# EncLickDrv_J0104132C-ESPrevC.net
KiCad netlist of a schematic drawn in EAGLE
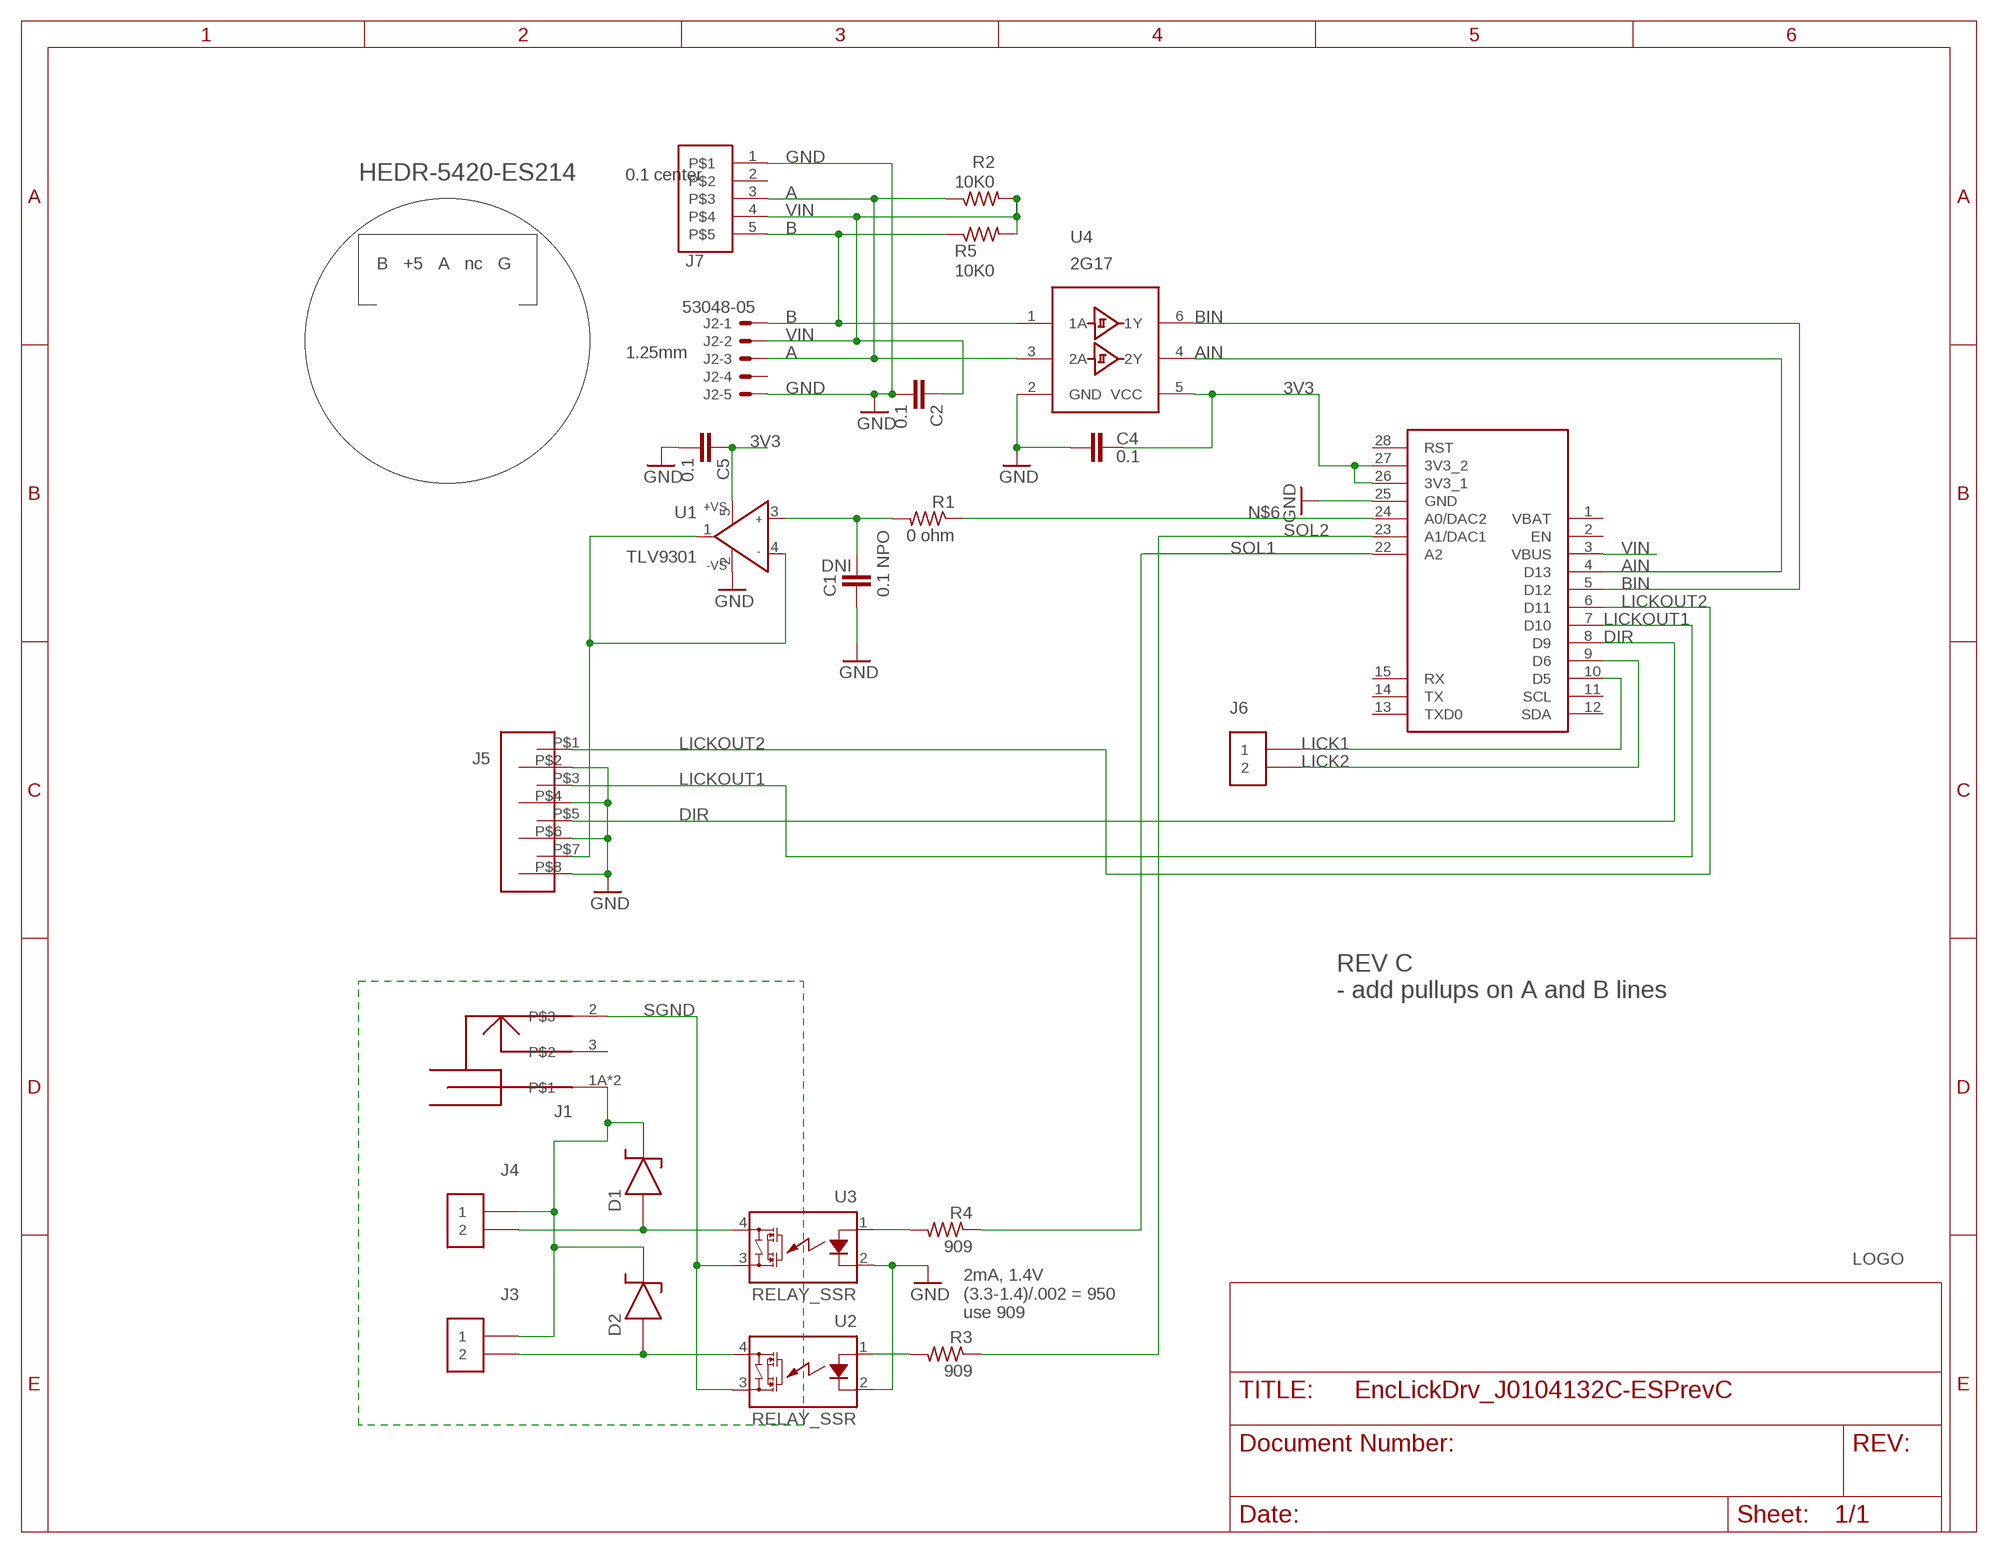
[diagram p0: schematic, sheet 1]

(export (version "E")
  (design (tool "Eeschema 10.0.6"))
  (components
    (comp (ref "C1")
      (value "0.1 NPO")
      (footprint "eagle-import:1206S")
      (libsource (lib "eagle-import") (part "CAPS1206S"))
    )
    (comp (ref "C2")
      (value "0.1")
      (footprint "eagle-import:0603S")
      (libsource (lib "eagle-import") (part "CAPS0603S"))
    )
    (comp (ref "C4")
      (value "0.1")
      (footprint "eagle-import:0603S")
      (libsource (lib "eagle-import") (part "CAPS0603S"))
    )
    (comp (ref "C5")
      (value "0.1")
      (footprint "eagle-import:0603S")
      (libsource (lib "eagle-import") (part "CAPS0603S"))
    )
    (comp (ref "D1")
      (value "DIODE_SCHOTTKYPWRDI-123")
      (footprint "eagle-import:PWRDI-123")
      (libsource (lib "eagle-import") (part "DIODE_SCHOTTKYPWRDI-123"))
    )
    (comp (ref "D2")
      (value "DIODE_SCHOTTKYPWRDI-123")
      (footprint "eagle-import:PWRDI-123")
      (libsource (lib "eagle-import") (part "DIODE_SCHOTTKYPWRDI-123"))
    )
    (comp (ref "J1")
      (value "POWER_JACK_SHUNTPJ-002")
      (footprint "eagle-import:PJ-002")
      (libsource (lib "eagle-import") (part "POWER_JACK_SHUNTPJ-002"))
    )
    (comp (ref "J2")
      (value "53048-05")
      (footprint "eagle-import:53048-05")
      (fields (field (name "MF") "MOLEX") (field (name "MPN") "53048-0510"))
      (libsource (lib "eagle-import") (part "53?-05048"))
    )
    (comp (ref "J3")
      (value "CON21881558")
      (footprint "eagle-import:1881558")
      (libsource (lib "eagle-import") (part "CON21881558"))
    )
    (comp (ref "J4")
      (value "CON21881558")
      (footprint "eagle-import:1881558")
      (libsource (lib "eagle-import") (part "CON21881558"))
    )
    (comp (ref "J5")
      (value "CON81844743")
      (footprint "eagle-import:1844743")
      (libsource (lib "eagle-import") (part "CON81844743"))
    )
    (comp (ref "J6")
      (value "CON21881558")
      (footprint "eagle-import:1881558")
      (libsource (lib "eagle-import") (part "CON21881558"))
    )
    (comp (ref "J7")
      (value "CON5104361-4")
      (footprint "eagle-import:104361-4")
      (libsource (lib "eagle-import") (part "CON5104361-4"))
    )
    (comp (ref "M1")
      (value "ESP32=S2-REV-TFT-NO16-21")
      (footprint "eagle-import:ESP32-S2-REV-TFT-NO16-21")
      (libsource (lib "eagle-import") (part "ESP32=S2-REV-TFT-NO16-21"))
    )
    (comp (ref "R1")
      (value "0 ohm")
      (footprint "eagle-import:0805S")
      (libsource (lib "eagle-import") (part "RESISTOR_SM0805S"))
    )
    (comp (ref "R2")
      (value "10K0")
      (footprint "eagle-import:0805S")
      (libsource (lib "eagle-import") (part "RESISTOR_SM0805S"))
    )
    (comp (ref "R3")
      (value "909")
      (footprint "eagle-import:0805S")
      (libsource (lib "eagle-import") (part "RESISTOR_SM0805S"))
    )
    (comp (ref "R4")
      (value "909")
      (footprint "eagle-import:0805S")
      (libsource (lib "eagle-import") (part "RESISTOR_SM0805S"))
    )
    (comp (ref "R5")
      (value "10K0")
      (footprint "eagle-import:0805S")
      (libsource (lib "eagle-import") (part "RESISTOR_SM0805S"))
    )
    (comp (ref "U$1")
      (value "JFRC-LOGOLOGO_OP")
      (footprint "eagle-import:LOGO_BMP_OP")
      (libsource (lib "eagle-import") (part "JFRC-LOGOLOGO_OP"))
    )
    (comp (ref "U1")
      (value "TLV9301")
      (footprint "eagle-import:SOT23-5")
      (fields (field (name "MF") "ALTERA CORPORATION") (field (name "MPN") "AD8065ARTZ-REEL7"))
      (libsource (lib "eagle-import") (part "AD8065RT"))
    )
    (comp (ref "U2")
      (value "RELAY_SSR")
      (footprint "eagle-import:SSR_SOIP")
      (libsource (lib "eagle-import") (part "RELAY_SSR"))
    )
    (comp (ref "U3")
      (value "RELAY_SSR")
      (footprint "eagle-import:SSR_SOIP")
      (libsource (lib "eagle-import") (part "RELAY_SSR"))
    )
    (comp (ref "U4")
      (value "2G17")
      (footprint "eagle-import:SOT23-6")
      (libsource (lib "eagle-import") (part "2G17"))
    )
  )
  (nets
    (net (code "1") (name "/3V3") (class "Default")
      (node (ref "C4") (pin "1") (pinfunction "1_1") (pintype "passive"))
      (node (ref "C5") (pin "1") (pinfunction "1_1") (pintype "passive"))
      (node (ref "M1") (pin "26") (pinfunction "3V3_1_26") (pintype "bidirectional"))
      (node (ref "M1") (pin "27") (pinfunction "3V3_2_27") (pintype "bidirectional"))
      (node (ref "U1") (pin "5") (pinfunction "+VS_5") (pintype "input"))
      (node (ref "U4") (pin "5") (pinfunction "VCC_5") (pintype "bidirectional"))
    )
    (net (code "2") (name "/A") (class "Default")
      (node (ref "J2") (pin "3") (pinfunction "S_3") (pintype "passive"))
      (node (ref "J7") (pin "3") (pinfunction "P$3_3") (pintype "bidirectional"))
      (node (ref "R2") (pin "1") (pinfunction "1_1") (pintype "passive"))
      (node (ref "U4") (pin "3") (pinfunction "2A_3") (pintype "bidirectional"))
    )
    (net (code "3") (name "/AIN") (class "Default")
      (node (ref "M1") (pin "4") (pinfunction "D13_4") (pintype "bidirectional"))
      (node (ref "U4") (pin "4") (pinfunction "2Y_4") (pintype "bidirectional"))
    )
    (net (code "4") (name "/B") (class "Default")
      (node (ref "J2") (pin "1") (pinfunction "S_1") (pintype "passive"))
      (node (ref "J7") (pin "5") (pinfunction "P$5_5") (pintype "bidirectional"))
      (node (ref "R5") (pin "1") (pinfunction "1_1") (pintype "passive"))
      (node (ref "U4") (pin "1") (pinfunction "1A_1") (pintype "bidirectional"))
    )
    (net (code "5") (name "/BIN") (class "Default")
      (node (ref "M1") (pin "5") (pinfunction "D12_5") (pintype "bidirectional"))
      (node (ref "U4") (pin "6") (pinfunction "1Y_6") (pintype "bidirectional"))
    )
    (net (code "6") (name "/DIR") (class "Default")
      (node (ref "J5") (pin "P$5") (pinfunction "5_P$5") (pintype "bidirectional"))
      (node (ref "M1") (pin "8") (pinfunction "D9_8") (pintype "bidirectional"))
    )
    (net (code "7") (name "/LICK1") (class "Default")
      (node (ref "J6") (pin "1") (pinfunction "1_1") (pintype "bidirectional"))
      (node (ref "M1") (pin "10") (pinfunction "D5_10") (pintype "bidirectional"))
    )
    (net (code "8") (name "/LICK2") (class "Default")
      (node (ref "J6") (pin "2") (pinfunction "2_2") (pintype "bidirectional"))
      (node (ref "M1") (pin "9") (pinfunction "D6_9") (pintype "bidirectional"))
    )
    (net (code "9") (name "/LICKOUT1") (class "Default")
      (node (ref "J5") (pin "P$3") (pinfunction "3_P$3") (pintype "bidirectional"))
      (node (ref "M1") (pin "7") (pinfunction "D10_7") (pintype "bidirectional"))
    )
    (net (code "10") (name "/LICKOUT2") (class "Default")
      (node (ref "J5") (pin "P$1") (pinfunction "1_P$1") (pintype "bidirectional"))
      (node (ref "M1") (pin "6") (pinfunction "D11_6") (pintype "bidirectional"))
    )
    (net (code "11") (name "/N$6") (class "Default")
      (node (ref "M1") (pin "24") (pinfunction "A0/DAC2_24") (pintype "bidirectional"))
      (node (ref "R1") (pin "1") (pinfunction "1_1") (pintype "passive"))
    )
    (net (code "12") (name "/SGND") (class "Default")
      (node (ref "J1") (pin "2") (pinfunction "P$3_2") (pintype "bidirectional"))
      (node (ref "U2") (pin "3") (pinfunction "DS2_3") (pintype "passive"))
      (node (ref "U3") (pin "3") (pinfunction "DS2_3") (pintype "passive"))
    )
    (net (code "13") (name "/SOL1") (class "Default")
      (node (ref "M1") (pin "22") (pinfunction "A2_22") (pintype "bidirectional"))
      (node (ref "R4") (pin "1") (pinfunction "1_1") (pintype "passive"))
    )
    (net (code "14") (name "/SOL2") (class "Default")
      (node (ref "M1") (pin "23") (pinfunction "A1/DAC1_23") (pintype "bidirectional"))
      (node (ref "R3") (pin "1") (pinfunction "1_1") (pintype "passive"))
    )
    (net (code "15") (name "/VIN") (class "Default")
      (node (ref "C2") (pin "1") (pinfunction "1_1") (pintype "passive"))
      (node (ref "J2") (pin "2") (pinfunction "S_2") (pintype "passive"))
      (node (ref "J7") (pin "4") (pinfunction "P$4_4") (pintype "bidirectional"))
      (node (ref "M1") (pin "3") (pinfunction "VBUS_3") (pintype "bidirectional"))
      (node (ref "R2") (pin "2") (pinfunction "2_2") (pintype "passive"))
      (node (ref "R5") (pin "2") (pinfunction "2_2") (pintype "passive"))
    )
    (net (code "16") (name "GND") (class "Default")
      (node (ref "C1") (pin "2") (pinfunction "2_2") (pintype "passive"))
      (node (ref "C2") (pin "2") (pinfunction "2_2") (pintype "passive"))
      (node (ref "C4") (pin "2") (pinfunction "2_2") (pintype "passive"))
      (node (ref "C5") (pin "2") (pinfunction "2_2") (pintype "passive"))
      (node (ref "J2") (pin "5") (pinfunction "S_5") (pintype "passive"))
      (node (ref "J5") (pin "P$2") (pinfunction "2_P$2") (pintype "bidirectional"))
      (node (ref "J5") (pin "P$4") (pinfunction "4_P$4") (pintype "bidirectional"))
      (node (ref "J5") (pin "P$6") (pinfunction "6_P$6") (pintype "bidirectional"))
      (node (ref "J5") (pin "P$8") (pinfunction "8_P$8") (pintype "bidirectional"))
      (node (ref "J7") (pin "1") (pinfunction "P$1_1") (pintype "bidirectional"))
      (node (ref "M1") (pin "25") (pinfunction "GND_25") (pintype "bidirectional"))
      (node (ref "U1") (pin "2") (pinfunction "-VS_2") (pintype "input"))
      (node (ref "U2") (pin "2") (pinfunction "K_2") (pintype "passive"))
      (node (ref "U3") (pin "2") (pinfunction "K_2") (pintype "passive"))
      (node (ref "U4") (pin "2") (pinfunction "GND_2") (pintype "bidirectional"))
    )
    (net (code "17") (name "Net-(D1-PadK)") (class "Default")
      (node (ref "D1") (pin "K") (pinfunction "K_K") (pintype "bidirectional"))
      (node (ref "D2") (pin "K") (pinfunction "K_K") (pintype "bidirectional"))
      (node (ref "J1") (pin "1A") (pinfunction "P$1_1A") (pintype "bidirectional"))
      (node (ref "J1") (pin "1B") (pinfunction "P$1_1B") (pintype "bidirectional"))
      (node (ref "J3") (pin "1") (pinfunction "1_1") (pintype "bidirectional"))
      (node (ref "J4") (pin "1") (pinfunction "1_1") (pintype "bidirectional"))
    )
    (net (code "18") (name "Net-(J5-7)") (class "Default")
      (node (ref "J5") (pin "P$7") (pinfunction "7_P$7") (pintype "bidirectional"))
      (node (ref "U1") (pin "1") (pinfunction "OUT_1") (pintype "output"))
      (node (ref "U1") (pin "4") (pinfunction "IN-_4") (pintype "input"))
    )
    (net (code "19") (name "Net-(U1-IN+)") (class "Default")
      (node (ref "C1") (pin "1") (pinfunction "1_1") (pintype "passive"))
      (node (ref "R1") (pin "2") (pinfunction "2_2") (pintype "passive"))
      (node (ref "U1") (pin "3") (pinfunction "IN+_3") (pintype "input"))
    )
    (net (code "20") (name "Net-(U2-A)") (class "Default")
      (node (ref "R3") (pin "2") (pinfunction "2_2") (pintype "passive"))
      (node (ref "U2") (pin "1") (pinfunction "A_1") (pintype "passive"))
    )
    (net (code "21") (name "Net-(U2-DS1)") (class "Default")
      (node (ref "D2") (pin "A") (pinfunction "A_A") (pintype "bidirectional"))
      (node (ref "J3") (pin "2") (pinfunction "2_2") (pintype "bidirectional"))
      (node (ref "U2") (pin "4") (pinfunction "DS1_4") (pintype "passive"))
    )
    (net (code "22") (name "Net-(U3-A)") (class "Default")
      (node (ref "R4") (pin "2") (pinfunction "2_2") (pintype "passive"))
      (node (ref "U3") (pin "1") (pinfunction "A_1") (pintype "passive"))
    )
    (net (code "23") (name "Net-(U3-DS1)") (class "Default")
      (node (ref "D1") (pin "A") (pinfunction "A_A") (pintype "bidirectional"))
      (node (ref "J4") (pin "2") (pinfunction "2_2") (pintype "bidirectional"))
      (node (ref "U3") (pin "4") (pinfunction "DS1_4") (pintype "passive"))
    )
    (net (code "24") (name "unconnected-(J1-P$2-Pad3)") (class "Default")
      (node (ref "J1") (pin "3") (pinfunction "P$2_3") (pintype "bidirectional"))
    )
    (net (code "25") (name "unconnected-(J2D-S-Pad4)") (class "Default")
      (node (ref "J2") (pin "4") (pinfunction "S_4") (pintype "passive"))
    )
    (net (code "26") (name "unconnected-(J7-P$2-Pad2)") (class "Default")
      (node (ref "J7") (pin "2") (pinfunction "P$2_2") (pintype "bidirectional"))
    )
    (net (code "27") (name "unconnected-(M1-EN-Pad2)") (class "Default")
      (node (ref "M1") (pin "2") (pinfunction "EN_2") (pintype "bidirectional"))
    )
    (net (code "28") (name "unconnected-(M1-RST-Pad28)") (class "Default")
      (node (ref "M1") (pin "28") (pinfunction "RST_28") (pintype "bidirectional"))
    )
    (net (code "29") (name "unconnected-(M1-RX-Pad15)") (class "Default")
      (node (ref "M1") (pin "15") (pinfunction "RX_15") (pintype "bidirectional"))
    )
    (net (code "30") (name "unconnected-(M1-SCL-Pad11)") (class "Default")
      (node (ref "M1") (pin "11") (pinfunction "SCL_11") (pintype "bidirectional"))
    )
    (net (code "31") (name "unconnected-(M1-SDA-Pad12)") (class "Default")
      (node (ref "M1") (pin "12") (pinfunction "SDA_12") (pintype "bidirectional"))
    )
    (net (code "32") (name "unconnected-(M1-TX-Pad14)") (class "Default")
      (node (ref "M1") (pin "14") (pinfunction "TX_14") (pintype "bidirectional"))
    )
    (net (code "33") (name "unconnected-(M1-TXD0-Pad13)") (class "Default")
      (node (ref "M1") (pin "13") (pinfunction "TXD0_13") (pintype "bidirectional"))
    )
    (net (code "34") (name "unconnected-(M1-VBAT-Pad1)") (class "Default")
      (node (ref "M1") (pin "1") (pinfunction "VBAT_1") (pintype "bidirectional"))
    )
  )
)
